# FPGA.net
KiCad netlist of a schematic drawn in Altium Designer
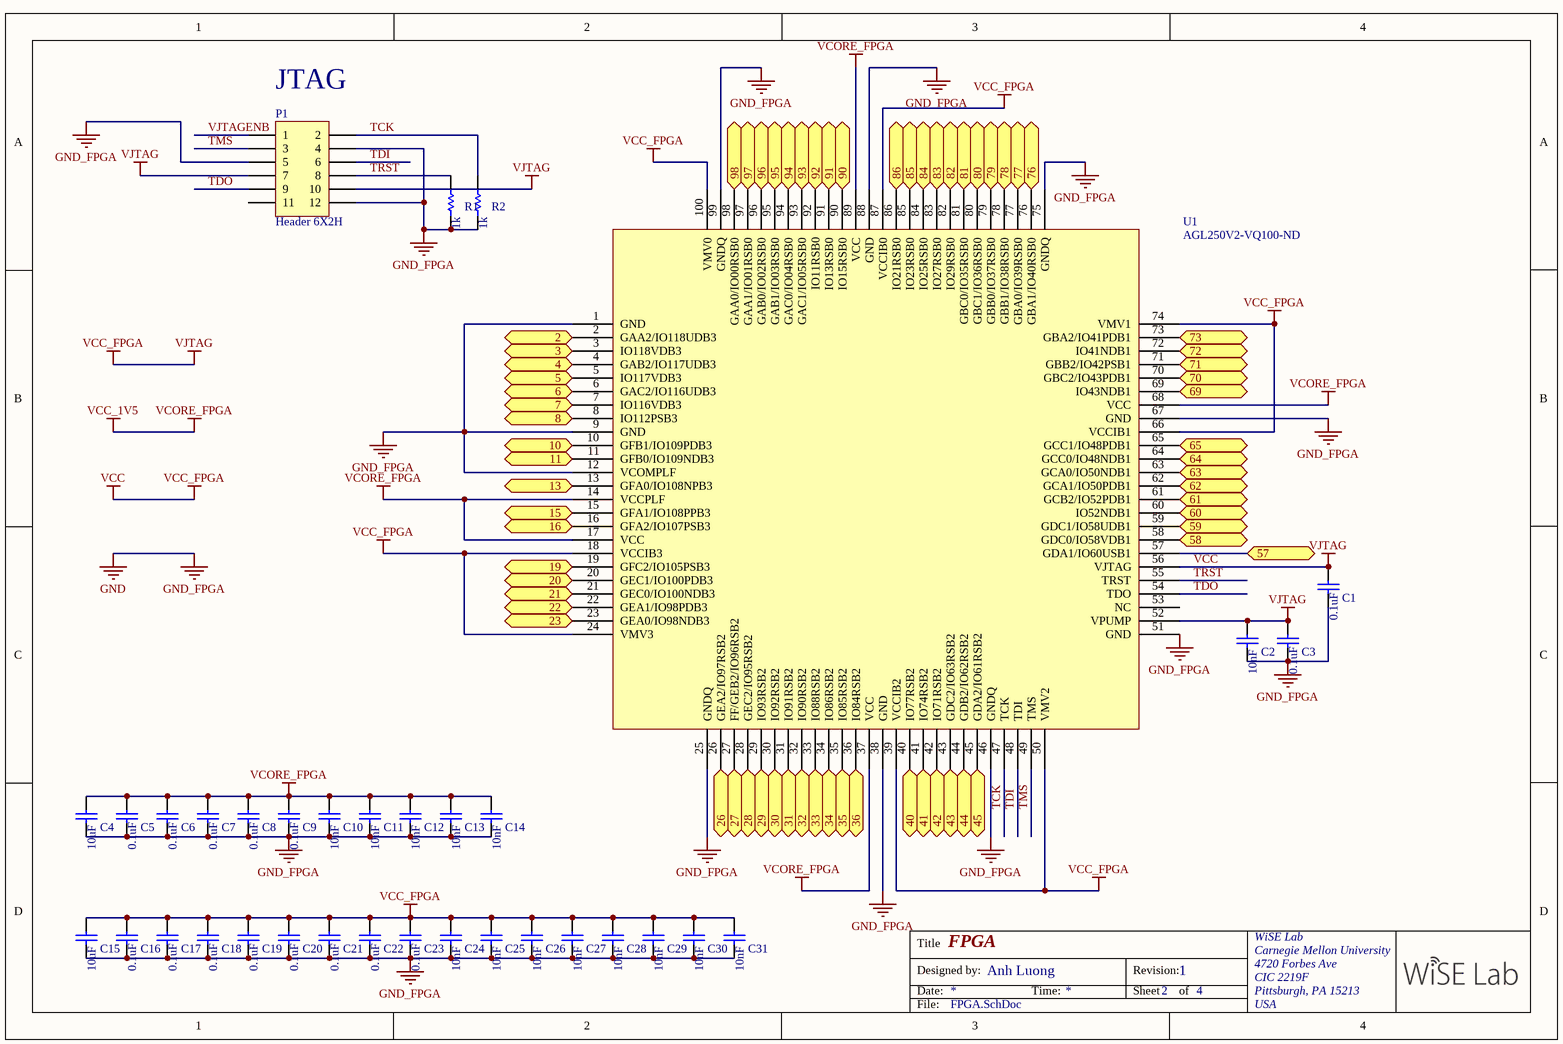
[diagram p0: FPGA.SchDoc]

(export (version "E")
  (design (tool "Eeschema 10.0.6"))
  (components
    (comp (ref "C1")
      (value "GRM155R71C104KA88D")
      (footprint "CAPC1005X04L")
      (description "CAP CER 0.1UF 16V X7R 0402")
      (fields
        (field (name "MANUFACTURER") "Murata Electronics North America")
        (field (name "TOLERANCE") "±10%")
      )
      (libsource (lib "Passives") (part "GRM155R71C104KA88D"))
    )
    (comp (ref "C2")
      (value "GRM155R71E103KA01D")
      (footprint "CAPC1005X04L")
      (description "CAP CER 10000PF 25V X7R 0402")
      (fields
        (field (name "MANUFACTURER") "Murata Electronics North America")
        (field (name "TOLERANCE") "±10%")
      )
      (libsource (lib "Passives") (part "GRM155R71E103KA01D"))
    )
    (comp (ref "C3")
      (value "GRM155R71C104KA88D")
      (footprint "CAPC1005X04L")
      (description "CAP CER 0.1UF 16V X7R 0402")
      (fields
        (field (name "MANUFACTURER") "Murata Electronics North America")
        (field (name "TOLERANCE") "±10%")
      )
      (libsource (lib "Passives") (part "GRM155R71C104KA88D"))
    )
    (comp (ref "C4")
      (value "GRM155R60J106ME15D")
      (footprint "INDC1005X04L")
      (description "CAP CER 10UF 6.3V X5R 0402")
      (fields
        (field (name "MANUFACTURER") "Murata Electronics North America")
        (field (name "TOLERANCE") "±20%")
      )
      (libsource (lib "Passives") (part "GRM155R60J106ME15D"))
    )
    (comp (ref "C5")
      (value "GRM155R71C104KA88D")
      (footprint "CAPC1005X04L")
      (description "CAP CER 0.1UF 16V X7R 0402")
      (fields
        (field (name "MANUFACTURER") "Murata Electronics North America")
        (field (name "TOLERANCE") "±10%")
      )
      (libsource (lib "Passives") (part "GRM155R71C104KA88D"))
    )
    (comp (ref "C6")
      (value "GRM155R71C104KA88D")
      (footprint "CAPC1005X04L")
      (description "CAP CER 0.1UF 16V X7R 0402")
      (fields
        (field (name "MANUFACTURER") "Murata Electronics North America")
        (field (name "TOLERANCE") "±10%")
      )
      (libsource (lib "Passives") (part "GRM155R71C104KA88D"))
    )
    (comp (ref "C7")
      (value "GRM155R71C104KA88D")
      (footprint "CAPC1005X04L")
      (description "CAP CER 0.1UF 16V X7R 0402")
      (fields
        (field (name "MANUFACTURER") "Murata Electronics North America")
        (field (name "TOLERANCE") "±10%")
      )
      (libsource (lib "Passives") (part "GRM155R71C104KA88D"))
    )
    (comp (ref "C8")
      (value "GRM155R71C104KA88D")
      (footprint "CAPC1005X04L")
      (description "CAP CER 0.1UF 16V X7R 0402")
      (fields
        (field (name "MANUFACTURER") "Murata Electronics North America")
        (field (name "TOLERANCE") "±10%")
      )
      (libsource (lib "Passives") (part "GRM155R71C104KA88D"))
    )
    (comp (ref "C9")
      (value "GRM155R71C104KA88D")
      (footprint "CAPC1005X04L")
      (description "CAP CER 0.1UF 16V X7R 0402")
      (fields
        (field (name "MANUFACTURER") "Murata Electronics North America")
        (field (name "TOLERANCE") "±10%")
      )
      (libsource (lib "Passives") (part "GRM155R71C104KA88D"))
    )
    (comp (ref "C10")
      (value "GRM155R71E103KA01D")
      (footprint "CAPC1005X04L")
      (description "CAP CER 10000PF 25V X7R 0402")
      (fields
        (field (name "MANUFACTURER") "Murata Electronics North America")
        (field (name "TOLERANCE") "±10%")
      )
      (libsource (lib "Passives") (part "GRM155R71E103KA01D"))
    )
    (comp (ref "C11")
      (value "GRM155R71E103KA01D")
      (footprint "CAPC1005X04L")
      (description "CAP CER 10000PF 25V X7R 0402")
      (fields
        (field (name "MANUFACTURER") "Murata Electronics North America")
        (field (name "TOLERANCE") "±10%")
      )
      (libsource (lib "Passives") (part "GRM155R71E103KA01D"))
    )
    (comp (ref "C12")
      (value "GRM155R71E103KA01D")
      (footprint "CAPC1005X04L")
      (description "CAP CER 10000PF 25V X7R 0402")
      (fields
        (field (name "MANUFACTURER") "Murata Electronics North America")
        (field (name "TOLERANCE") "±10%")
      )
      (libsource (lib "Passives") (part "GRM155R71E103KA01D"))
    )
    (comp (ref "C13")
      (value "GRM155R71E103KA01D")
      (footprint "CAPC1005X04L")
      (description "CAP CER 10000PF 25V X7R 0402")
      (fields
        (field (name "MANUFACTURER") "Murata Electronics North America")
        (field (name "TOLERANCE") "±10%")
      )
      (libsource (lib "Passives") (part "GRM155R71E103KA01D"))
    )
    (comp (ref "C14")
      (value "GRM155R71E103KA01D")
      (footprint "CAPC1005X04L")
      (description "CAP CER 10000PF 25V X7R 0402")
      (fields
        (field (name "MANUFACTURER") "Murata Electronics North America")
        (field (name "TOLERANCE") "±10%")
      )
      (libsource (lib "Passives") (part "GRM155R71E103KA01D"))
    )
    (comp (ref "C15")
      (value "GRM155R60J106ME15D")
      (footprint "INDC1005X04L")
      (description "CAP CER 10UF 6.3V X5R 0402")
      (fields
        (field (name "MANUFACTURER") "Murata Electronics North America")
        (field (name "TOLERANCE") "±20%")
      )
      (libsource (lib "Passives") (part "GRM155R60J106ME15D"))
    )
    (comp (ref "C16")
      (value "GRM155R71C104KA88D")
      (footprint "CAPC1005X04L")
      (description "CAP CER 0.1UF 16V X7R 0402")
      (fields
        (field (name "MANUFACTURER") "Murata Electronics North America")
        (field (name "TOLERANCE") "±10%")
      )
      (libsource (lib "Passives") (part "GRM155R71C104KA88D"))
    )
    (comp (ref "C17")
      (value "GRM155R71C104KA88D")
      (footprint "CAPC1005X04L")
      (description "CAP CER 0.1UF 16V X7R 0402")
      (fields
        (field (name "MANUFACTURER") "Murata Electronics North America")
        (field (name "TOLERANCE") "±10%")
      )
      (libsource (lib "Passives") (part "GRM155R71C104KA88D"))
    )
    (comp (ref "C18")
      (value "GRM155R71C104KA88D")
      (footprint "CAPC1005X04L")
      (description "CAP CER 0.1UF 16V X7R 0402")
      (fields
        (field (name "MANUFACTURER") "Murata Electronics North America")
        (field (name "TOLERANCE") "±10%")
      )
      (libsource (lib "Passives") (part "GRM155R71C104KA88D"))
    )
    (comp (ref "C19")
      (value "GRM155R71C104KA88D")
      (footprint "CAPC1005X04L")
      (description "CAP CER 0.1UF 16V X7R 0402")
      (fields
        (field (name "MANUFACTURER") "Murata Electronics North America")
        (field (name "TOLERANCE") "±10%")
      )
      (libsource (lib "Passives") (part "GRM155R71C104KA88D"))
    )
    (comp (ref "C20")
      (value "GRM155R71C104KA88D")
      (footprint "CAPC1005X04L")
      (description "CAP CER 0.1UF 16V X7R 0402")
      (fields
        (field (name "MANUFACTURER") "Murata Electronics North America")
        (field (name "TOLERANCE") "±10%")
      )
      (libsource (lib "Passives") (part "GRM155R71C104KA88D"))
    )
    (comp (ref "C21")
      (value "GRM155R71C104KA88D")
      (footprint "CAPC1005X04L")
      (description "CAP CER 0.1UF 16V X7R 0402")
      (fields
        (field (name "MANUFACTURER") "Murata Electronics North America")
        (field (name "TOLERANCE") "±10%")
      )
      (libsource (lib "Passives") (part "GRM155R71C104KA88D"))
    )
    (comp (ref "C22")
      (value "GRM155R71C104KA88D")
      (footprint "CAPC1005X04L")
      (description "CAP CER 0.1UF 16V X7R 0402")
      (fields
        (field (name "MANUFACTURER") "Murata Electronics North America")
        (field (name "TOLERANCE") "±10%")
      )
      (libsource (lib "Passives") (part "GRM155R71C104KA88D"))
    )
    (comp (ref "C23")
      (value "GRM155R71C104KA88D")
      (footprint "CAPC1005X04L")
      (description "CAP CER 0.1UF 16V X7R 0402")
      (fields
        (field (name "MANUFACTURER") "Murata Electronics North America")
        (field (name "TOLERANCE") "±10%")
      )
      (libsource (lib "Passives") (part "GRM155R71C104KA88D"))
    )
    (comp (ref "C24")
      (value "GRM155R71E103KA01D")
      (footprint "CAPC1005X04L")
      (description "CAP CER 10000PF 25V X7R 0402")
      (fields
        (field (name "MANUFACTURER") "Murata Electronics North America")
        (field (name "TOLERANCE") "±10%")
      )
      (libsource (lib "Passives") (part "GRM155R71E103KA01D"))
    )
    (comp (ref "C25")
      (value "GRM155R71E103KA01D")
      (footprint "CAPC1005X04L")
      (description "CAP CER 10000PF 25V X7R 0402")
      (fields
        (field (name "MANUFACTURER") "Murata Electronics North America")
        (field (name "TOLERANCE") "±10%")
      )
      (libsource (lib "Passives") (part "GRM155R71E103KA01D"))
    )
    (comp (ref "C26")
      (value "GRM155R71E103KA01D")
      (footprint "CAPC1005X04L")
      (description "CAP CER 10000PF 25V X7R 0402")
      (fields
        (field (name "MANUFACTURER") "Murata Electronics North America")
        (field (name "TOLERANCE") "±10%")
      )
      (libsource (lib "Passives") (part "GRM155R71E103KA01D"))
    )
    (comp (ref "C27")
      (value "GRM155R71E103KA01D")
      (footprint "CAPC1005X04L")
      (description "CAP CER 10000PF 25V X7R 0402")
      (fields
        (field (name "MANUFACTURER") "Murata Electronics North America")
        (field (name "TOLERANCE") "±10%")
      )
      (libsource (lib "Passives") (part "GRM155R71E103KA01D"))
    )
    (comp (ref "C28")
      (value "GRM155R71E103KA01D")
      (footprint "CAPC1005X04L")
      (description "CAP CER 10000PF 25V X7R 0402")
      (fields
        (field (name "MANUFACTURER") "Murata Electronics North America")
        (field (name "TOLERANCE") "±10%")
      )
      (libsource (lib "Passives") (part "GRM155R71E103KA01D"))
    )
    (comp (ref "C29")
      (value "GRM155R71E103KA01D")
      (footprint "CAPC1005X04L")
      (description "CAP CER 10000PF 25V X7R 0402")
      (fields
        (field (name "MANUFACTURER") "Murata Electronics North America")
        (field (name "TOLERANCE") "±10%")
      )
      (libsource (lib "Passives") (part "GRM155R71E103KA01D"))
    )
    (comp (ref "C30")
      (value "GRM155R71E103KA01D")
      (footprint "CAPC1005X04L")
      (description "CAP CER 10000PF 25V X7R 0402")
      (fields
        (field (name "MANUFACTURER") "Murata Electronics North America")
        (field (name "TOLERANCE") "±10%")
      )
      (libsource (lib "Passives") (part "GRM155R71E103KA01D"))
    )
    (comp (ref "C31")
      (value "GRM155R71E103KA01D")
      (footprint "CAPC1005X04L")
      (description "CAP CER 10000PF 25V X7R 0402")
      (fields
        (field (name "MANUFACTURER") "Murata Electronics North America")
        (field (name "TOLERANCE") "±10%")
      )
      (libsource (lib "Passives") (part "GRM155R71E103KA01D"))
    )
    (comp (ref "P1")
      (value "Header 6X2H")
      (footprint "HDR2X6H")
      (description "Header, 6-Pin, Dual row, Right Angle")
      (fields (field (name "PUBLISHER") "Altium Limited"))
      (libsource (lib "Miscellaneous Connectors") (part "Header 6X2H"))
    )
    (comp (ref "R1")
      (value "MCR01MRTF1001")
      (footprint "RESC1005X04N")
      (description "RES SMD 1K OHM 1% 1/16W 0402")
      (fields (field (name "MANUFACTURER") "Rohm Semiconductor") (field (name "TOLERANCE") "±1%"))
      (libsource (lib "Passives") (part "MCR01MRTF1001"))
    )
    (comp (ref "R2")
      (value "MCR01MRTF1001")
      (footprint "RESC1005X04N")
      (description "RES SMD 1K OHM 1% 1/16W 0402")
      (fields (field (name "MANUFACTURER") "Rohm Semiconductor") (field (name "TOLERANCE") "±1%"))
      (libsource (lib "Passives") (part "MCR01MRTF1001"))
    )
    (comp (ref "U1")
      (value "AGL250V2-VQ100")
      (footprint "TSQFP50P1600X1600X120-100N")
      (description "IC FPGA 68 I/O 100VQFP")
      (fields
        (field (name "MANUFACTURER") "Microsemi SoC")
        (field (name "SUPPLIER PART NUMBER 1") "AGL250V2-VQ100-ND")
      )
      (libsource (lib "Chronos") (part "AGL250V2-VQ100"))
    )
  )
  (nets
    (net (code "1") (name "/2") (class "Default")
      (node (ref "U1") (pin "2") (pinfunction "GAA2/IO118UDB3_2") (pintype "passive"))
    )
    (net (code "2") (name "/3") (class "Default")
      (node (ref "U1") (pin "3") (pinfunction "IO118VDB3_3") (pintype "passive"))
    )
    (net (code "3") (name "/4") (class "Default")
      (node (ref "U1") (pin "4") (pinfunction "GAB2/IO117UDB3_4") (pintype "passive"))
    )
    (net (code "4") (name "/5") (class "Default")
      (node (ref "U1") (pin "5") (pinfunction "IO117VDB3_5") (pintype "passive"))
    )
    (net (code "5") (name "/6") (class "Default")
      (node (ref "U1") (pin "6") (pinfunction "GAC2/IO116UDB3_6") (pintype "passive"))
    )
    (net (code "6") (name "/7") (class "Default")
      (node (ref "U1") (pin "7") (pinfunction "IO116VDB3_7") (pintype "passive"))
    )
    (net (code "7") (name "/8") (class "Default")
      (node (ref "U1") (pin "8") (pinfunction "IO112PSB3_8") (pintype "passive"))
    )
    (net (code "8") (name "/10") (class "Default")
      (node (ref "U1") (pin "10") (pinfunction "GFB1/IO109PDB3_10") (pintype "passive"))
    )
    (net (code "9") (name "/11") (class "Default")
      (node (ref "U1") (pin "11") (pinfunction "GFB0/IO109NDB3_11") (pintype "passive"))
    )
    (net (code "10") (name "/13") (class "Default")
      (node (ref "U1") (pin "13") (pinfunction "GFA0/IO108NPB3_13") (pintype "passive"))
    )
    (net (code "11") (name "/15") (class "Default")
      (node (ref "U1") (pin "15") (pinfunction "GFA1/IO108PPB3_15") (pintype "passive"))
    )
    (net (code "12") (name "/16") (class "Default")
      (node (ref "U1") (pin "16") (pinfunction "GFA2/IO107PSB3_16") (pintype "passive"))
    )
    (net (code "13") (name "/19") (class "Default")
      (node (ref "U1") (pin "19") (pinfunction "GFC2/IO105PSB3_19") (pintype "passive"))
    )
    (net (code "14") (name "/20") (class "Default")
      (node (ref "U1") (pin "20") (pinfunction "GEC1/IO100PDB3_20") (pintype "passive"))
    )
    (net (code "15") (name "/21") (class "Default")
      (node (ref "U1") (pin "21") (pinfunction "GEC0/IO100NDB3_21") (pintype "passive"))
    )
    (net (code "16") (name "/22") (class "Default")
      (node (ref "U1") (pin "22") (pinfunction "GEA1/IO98PDB3_22") (pintype "passive"))
    )
    (net (code "17") (name "/23") (class "Default")
      (node (ref "U1") (pin "23") (pinfunction "GEA0/IO98NDB3_23") (pintype "passive"))
    )
    (net (code "18") (name "/26") (class "Default")
      (node (ref "U1") (pin "26") (pinfunction "GEA2/IO97RSB2_26") (pintype "passive"))
    )
    (net (code "19") (name "/27") (class "Default")
      (node (ref "U1") (pin "27") (pinfunction "FF/GEB2/IO96RSB2_27") (pintype "passive"))
    )
    (net (code "20") (name "/28") (class "Default")
      (node (ref "U1") (pin "28") (pinfunction "GEC2/IO95RSB2_28") (pintype "passive"))
    )
    (net (code "21") (name "/29") (class "Default")
      (node (ref "U1") (pin "29") (pinfunction "IO93RSB2_29") (pintype "passive"))
    )
    (net (code "22") (name "/30") (class "Default")
      (node (ref "U1") (pin "30") (pinfunction "IO92RSB2_30") (pintype "passive"))
    )
    (net (code "23") (name "/31") (class "Default")
      (node (ref "U1") (pin "31") (pinfunction "IO91RSB2_31") (pintype "passive"))
    )
    (net (code "24") (name "/32") (class "Default")
      (node (ref "U1") (pin "32") (pinfunction "IO90RSB2_32") (pintype "passive"))
    )
    (net (code "25") (name "/33") (class "Default")
      (node (ref "U1") (pin "33") (pinfunction "IO88RSB2_33") (pintype "passive"))
    )
    (net (code "26") (name "/34") (class "Default")
      (node (ref "U1") (pin "34") (pinfunction "IO86RSB2_34") (pintype "passive"))
    )
    (net (code "27") (name "/35") (class "Default")
      (node (ref "U1") (pin "35") (pinfunction "IO85RSB2_35") (pintype "passive"))
    )
    (net (code "28") (name "/36") (class "Default")
      (node (ref "U1") (pin "36") (pinfunction "IO84RSB2_36") (pintype "passive"))
    )
    (net (code "29") (name "/40") (class "Default")
      (node (ref "U1") (pin "40") (pinfunction "IO77RSB2_40") (pintype "passive"))
    )
    (net (code "30") (name "/41") (class "Default")
      (node (ref "U1") (pin "41") (pinfunction "IO74RSB2_41") (pintype "passive"))
    )
    (net (code "31") (name "/42") (class "Default")
      (node (ref "U1") (pin "42") (pinfunction "IO71RSB2_42") (pintype "passive"))
    )
    (net (code "32") (name "/43") (class "Default")
      (node (ref "U1") (pin "43") (pinfunction "GDC2/IO63RSB2_43") (pintype "passive"))
    )
    (net (code "33") (name "/44") (class "Default")
      (node (ref "U1") (pin "44") (pinfunction "GDB2/IO62RSB2_44") (pintype "passive"))
    )
    (net (code "34") (name "/45") (class "Default")
      (node (ref "U1") (pin "45") (pinfunction "GDA2/IO61RSB2_45") (pintype "passive"))
    )
    (net (code "35") (name "/57") (class "Default")
      (node (ref "U1") (pin "57") (pinfunction "GDA1/IO60USB1_57") (pintype "passive"))
    )
    (net (code "36") (name "/58") (class "Default")
      (node (ref "U1") (pin "58") (pinfunction "GDC0/IO58VDB1_58") (pintype "passive"))
    )
    (net (code "37") (name "/59") (class "Default")
      (node (ref "U1") (pin "59") (pinfunction "GDC1/IO58UDB1_59") (pintype "passive"))
    )
    (net (code "38") (name "/60") (class "Default")
      (node (ref "U1") (pin "60") (pinfunction "IO52NDB1_60") (pintype "passive"))
    )
    (net (code "39") (name "/61") (class "Default")
      (node (ref "U1") (pin "61") (pinfunction "GCB2/IO52PDB1_61") (pintype "passive"))
    )
    (net (code "40") (name "/62") (class "Default")
      (node (ref "U1") (pin "62") (pinfunction "GCA1/IO50PDB1_62") (pintype "passive"))
    )
    (net (code "41") (name "/63") (class "Default")
      (node (ref "U1") (pin "63") (pinfunction "GCA0/IO50NDB1_63") (pintype "passive"))
    )
    (net (code "42") (name "/64") (class "Default")
      (node (ref "U1") (pin "64") (pinfunction "GCC0/IO48NDB1_64") (pintype "passive"))
    )
    (net (code "43") (name "/65") (class "Default")
      (node (ref "U1") (pin "65") (pinfunction "GCC1/IO48PDB1_65") (pintype "passive"))
    )
    (net (code "44") (name "/69") (class "Default")
      (node (ref "U1") (pin "69") (pinfunction "IO43NDB1_69") (pintype "passive"))
    )
    (net (code "45") (name "/70") (class "Default")
      (node (ref "U1") (pin "70") (pinfunction "GBC2/IO43PDB1_70") (pintype "passive"))
    )
    (net (code "46") (name "/71") (class "Default")
      (node (ref "U1") (pin "71") (pinfunction "GBB2/IO42PSB1_71") (pintype "passive"))
    )
    (net (code "47") (name "/72") (class "Default")
      (node (ref "U1") (pin "72") (pinfunction "IO41NDB1_72") (pintype "passive"))
    )
    (net (code "48") (name "/73") (class "Default")
      (node (ref "U1") (pin "73") (pinfunction "GBA2/IO41PDB1_73") (pintype "passive"))
    )
    (net (code "49") (name "/76") (class "Default")
      (node (ref "U1") (pin "76") (pinfunction "GBA1/IO40RSB0_76") (pintype "passive"))
    )
    (net (code "50") (name "/77") (class "Default")
      (node (ref "U1") (pin "77") (pinfunction "GBA0/IO39RSB0_77") (pintype "passive"))
    )
    (net (code "51") (name "/78") (class "Default")
      (node (ref "U1") (pin "78") (pinfunction "GBB1/IO38RSB0_78") (pintype "passive"))
    )
    (net (code "52") (name "/79") (class "Default")
      (node (ref "U1") (pin "79") (pinfunction "GBB0/IO37RSB0_79") (pintype "passive"))
    )
    (net (code "53") (name "/80") (class "Default")
      (node (ref "U1") (pin "80") (pinfunction "GBC1/IO36RSB0_80") (pintype "passive"))
    )
    (net (code "54") (name "/81") (class "Default")
      (node (ref "U1") (pin "81") (pinfunction "GBC0/IO35RSB0_81") (pintype "passive"))
    )
    (net (code "55") (name "/82") (class "Default")
      (node (ref "U1") (pin "82") (pinfunction "IO29RSB0_82") (pintype "passive"))
    )
    (net (code "56") (name "/83") (class "Default")
      (node (ref "U1") (pin "83") (pinfunction "IO27RSB0_83") (pintype "passive"))
    )
    (net (code "57") (name "/84") (class "Default")
      (node (ref "U1") (pin "84") (pinfunction "IO25RSB0_84") (pintype "passive"))
    )
    (net (code "58") (name "/85") (class "Default")
      (node (ref "U1") (pin "85") (pinfunction "IO23RSB0_85") (pintype "passive"))
    )
    (net (code "59") (name "/86") (class "Default")
      (node (ref "U1") (pin "86") (pinfunction "IO21RSB0_86") (pintype "passive"))
    )
    (net (code "60") (name "/90") (class "Default")
      (node (ref "U1") (pin "90") (pinfunction "IO15RSB0_90") (pintype "passive"))
    )
    (net (code "61") (name "/91") (class "Default")
      (node (ref "U1") (pin "91") (pinfunction "IO13RSB0_91") (pintype "passive"))
    )
    (net (code "62") (name "/92") (class "Default")
      (node (ref "U1") (pin "92") (pinfunction "IO11RSB0_92") (pintype "passive"))
    )
    (net (code "63") (name "/93") (class "Default")
      (node (ref "U1") (pin "93") (pinfunction "GAC1/IO05RSB0_93") (pintype "passive"))
    )
    (net (code "64") (name "/94") (class "Default")
      (node (ref "U1") (pin "94") (pinfunction "GAC0/IO04RSB0_94") (pintype "passive"))
    )
    (net (code "65") (name "/95") (class "Default")
      (node (ref "U1") (pin "95") (pinfunction "GAB1/IO03RSB0_95") (pintype "passive"))
    )
    (net (code "66") (name "/96") (class "Default")
      (node (ref "U1") (pin "96") (pinfunction "GAB0/IO02RSB0_96") (pintype "passive"))
    )
    (net (code "67") (name "/97") (class "Default")
      (node (ref "U1") (pin "97") (pinfunction "GAA1/IO01RSB0_97") (pintype "passive"))
    )
    (net (code "68") (name "/98") (class "Default")
      (node (ref "U1") (pin "98") (pinfunction "GAA0/IO00RSB0_98") (pintype "passive"))
    )
    (net (code "69") (name "/TCK") (class "Default")
      (node (ref "P1") (pin "2") (pinfunction "2_2") (pintype "passive"))
      (node (ref "R2") (pin "2") (pinfunction "2_2") (pintype "passive"))
      (node (ref "U1") (pin "47") (pinfunction "TCK_47") (pintype "passive"))
    )
    (net (code "70") (name "/TDI") (class "Default")
      (node (ref "P1") (pin "6") (pinfunction "6_6") (pintype "passive"))
      (node (ref "U1") (pin "48") (pinfunction "TDI_48") (pintype "passive"))
    )
    (net (code "71") (name "/TDO") (class "Default")
      (node (ref "P1") (pin "9") (pinfunction "9_9") (pintype "passive"))
      (node (ref "U1") (pin "54") (pinfunction "TDO_54") (pintype "passive"))
    )
    (net (code "72") (name "/TMS") (class "Default")
      (node (ref "P1") (pin "3") (pinfunction "3_3") (pintype "passive"))
      (node (ref "U1") (pin "49") (pinfunction "TMS_49") (pintype "passive"))
    )
    (net (code "73") (name "/TRST") (class "Default")
      (node (ref "P1") (pin "8") (pinfunction "8_8") (pintype "passive"))
      (node (ref "R1") (pin "2") (pinfunction "2_2") (pintype "passive"))
      (node (ref "U1") (pin "55") (pinfunction "TRST_55") (pintype "passive"))
    )
    (net (code "74") (name "/VJTAGENB") (class "Default")
      (node (ref "P1") (pin "1") (pinfunction "1_1") (pintype "passive"))
    )
    (net (code "75") (name "GND") (class "Default")
      (node (ref "C1") (pin "1") (pinfunction "1_1") (pintype "passive"))
      (node (ref "C10") (pin "1") (pinfunction "1_1") (pintype "passive"))
      (node (ref "C11") (pin "1") (pinfunction "1_1") (pintype "passive"))
      (node (ref "C12") (pin "1") (pinfunction "1_1") (pintype "passive"))
      (node (ref "C13") (pin "1") (pinfunction "1_1") (pintype "passive"))
      (node (ref "C14") (pin "1") (pinfunction "1_1") (pintype "passive"))
      (node (ref "C15") (pin "1") (pinfunction "1_1") (pintype "passive"))
      (node (ref "C16") (pin "1") (pinfunction "1_1") (pintype "passive"))
      (node (ref "C17") (pin "1") (pinfunction "1_1") (pintype "passive"))
      (node (ref "C18") (pin "1") (pinfunction "1_1") (pintype "passive"))
      (node (ref "C19") (pin "1") (pinfunction "1_1") (pintype "passive"))
      (node (ref "C2") (pin "1") (pinfunction "1_1") (pintype "passive"))
      (node (ref "C20") (pin "1") (pinfunction "1_1") (pintype "passive"))
      (node (ref "C21") (pin "1") (pinfunction "1_1") (pintype "passive"))
      (node (ref "C22") (pin "1") (pinfunction "1_1") (pintype "passive"))
      (node (ref "C23") (pin "1") (pinfunction "1_1") (pintype "passive"))
      (node (ref "C24") (pin "1") (pinfunction "1_1") (pintype "passive"))
      (node (ref "C25") (pin "1") (pinfunction "1_1") (pintype "passive"))
      (node (ref "C26") (pin "1") (pinfunction "1_1") (pintype "passive"))
      (node (ref "C27") (pin "1") (pinfunction "1_1") (pintype "passive"))
      (node (ref "C28") (pin "1") (pinfunction "1_1") (pintype "passive"))
      (node (ref "C29") (pin "1") (pinfunction "1_1") (pintype "passive"))
      (node (ref "C3") (pin "1") (pinfunction "1_1") (pintype "passive"))
      (node (ref "C30") (pin "1") (pinfunction "1_1") (pintype "passive"))
      (node (ref "C31") (pin "1") (pinfunction "1_1") (pintype "passive"))
      (node (ref "C4") (pin "1") (pinfunction "1_1") (pintype "passive"))
      (node (ref "C5") (pin "1") (pinfunction "1_1") (pintype "passive"))
      (node (ref "C6") (pin "1") (pinfunction "1_1") (pintype "passive"))
      (node (ref "C7") (pin "1") (pinfunction "1_1") (pintype "passive"))
      (node (ref "C8") (pin "1") (pinfunction "1_1") (pintype "passive"))
      (node (ref "C9") (pin "1") (pinfunction "1_1") (pintype "passive"))
      (node (ref "P1") (pin "12") (pinfunction "12_12") (pintype "passive"))
      (node (ref "P1") (pin "4") (pinfunction "4_4") (pintype "passive"))
      (node (ref "P1") (pin "5") (pinfunction "5_5") (pintype "passive"))
      (node (ref "R1") (pin "1") (pinfunction "1_1") (pintype "passive"))
      (node (ref "R2") (pin "1") (pinfunction "1_1") (pintype "passive"))
      (node (ref "U1") (pin "1") (pinfunction "GND_1") (pintype "passive"))
      (node (ref "U1") (pin "12") (pinfunction "VCOMPLF_12") (pintype "passive"))
      (node (ref "U1") (pin "25") (pinfunction "GNDQ_25") (pintype "passive"))
      (node (ref "U1") (pin "38") (pinfunction "GND_38") (pintype "passive"))
      (node (ref "U1") (pin "46") (pinfunction "GNDQ_46") (pintype "passive"))
      (node (ref "U1") (pin "51") (pinfunction "GND_51") (pintype "passive"))
      (node (ref "U1") (pin "67") (pinfunction "GND_67") (pintype "passive"))
      (node (ref "U1") (pin "75") (pinfunction "GNDQ_75") (pintype "passive"))
      (node (ref "U1") (pin "88") (pinfunction "GND_88") (pintype "passive"))
      (node (ref "U1") (pin "9") (pinfunction "GND_9") (pintype "passive"))
      (node (ref "U1") (pin "99") (pinfunction "GNDQ_99") (pintype "passive"))
    )
    (net (code "76") (name "VCC") (class "Default")
      (node (ref "C1") (pin "2") (pinfunction "2_2") (pintype "passive"))
      (node (ref "C15") (pin "2") (pinfunction "2_2") (pintype "passive"))
      (node (ref "C16") (pin "2") (pinfunction "2_2") (pintype "passive"))
      (node (ref "C17") (pin "2") (pinfunction "2_2") (pintype "passive"))
      (node (ref "C18") (pin "2") (pinfunction "2_2") (pintype "passive"))
      (node (ref "C19") (pin "2") (pinfunction "2_2") (pintype "passive"))
      (node (ref "C2") (pin "2") (pinfunction "2_2") (pintype "passive"))
      (node (ref "C20") (pin "2") (pinfunction "2_2") (pintype "passive"))
      (node (ref "C21") (pin "2") (pinfunction "2_2") (pintype "passive"))
      (node (ref "C22") (pin "2") (pinfunction "2_2") (pintype "passive"))
      (node (ref "C23") (pin "2") (pinfunction "2_2") (pintype "passive"))
      (node (ref "C24") (pin "2") (pinfunction "2_2") (pintype "passive"))
      (node (ref "C25") (pin "2") (pinfunction "2_2") (pintype "passive"))
      (node (ref "C26") (pin "2") (pinfunction "2_2") (pintype "passive"))
      (node (ref "C27") (pin "2") (pinfunction "2_2") (pintype "passive"))
      (node (ref "C28") (pin "2") (pinfunction "2_2") (pintype "passive"))
      (node (ref "C29") (pin "2") (pinfunction "2_2") (pintype "passive"))
      (node (ref "C3") (pin "2") (pinfunction "2_2") (pintype "passive"))
      (node (ref "C30") (pin "2") (pinfunction "2_2") (pintype "passive"))
      (node (ref "C31") (pin "2") (pinfunction "2_2") (pintype "passive"))
      (node (ref "P1") (pin "10") (pinfunction "10_10") (pintype "passive"))
      (node (ref "P1") (pin "7") (pinfunction "7_7") (pintype "passive"))
      (node (ref "U1") (pin "100") (pinfunction "VMV0_100") (pintype "passive"))
      (node (ref "U1") (pin "18") (pinfunction "VCCIB3_18") (pintype "passive"))
      (node (ref "U1") (pin "24") (pinfunction "VMV3_24") (pintype "passive"))
      (node (ref "U1") (pin "39") (pinfunction "VCCIB2_39") (pintype "passive"))
      (node (ref "U1") (pin "50") (pinfunction "VMV2_50") (pintype "passive"))
      (node (ref "U1") (pin "52") (pinfunction "VPUMP_52") (pintype "passive"))
      (node (ref "U1") (pin "56") (pinfunction "VJTAG_56") (pintype "passive"))
      (node (ref "U1") (pin "66") (pinfunction "VCCIB1_66") (pintype "passive"))
      (node (ref "U1") (pin "74") (pinfunction "VMV1_74") (pintype "passive"))
      (node (ref "U1") (pin "87") (pinfunction "VCCIB0_87") (pintype "passive"))
    )
    (net (code "77") (name "VCC_1V5") (class "Default")
      (node (ref "C10") (pin "2") (pinfunction "2_2") (pintype "passive"))
      (node (ref "C11") (pin "2") (pinfunction "2_2") (pintype "passive"))
      (node (ref "C12") (pin "2") (pinfunction "2_2") (pintype "passive"))
      (node (ref "C13") (pin "2") (pinfunction "2_2") (pintype "passive"))
      (node (ref "C14") (pin "2") (pinfunction "2_2") (pintype "passive"))
      (node (ref "C4") (pin "2") (pinfunction "2_2") (pintype "passive"))
      (node (ref "C5") (pin "2") (pinfunction "2_2") (pintype "passive"))
      (node (ref "C6") (pin "2") (pinfunction "2_2") (pintype "passive"))
      (node (ref "C7") (pin "2") (pinfunction "2_2") (pintype "passive"))
      (node (ref "C8") (pin "2") (pinfunction "2_2") (pintype "passive"))
      (node (ref "C9") (pin "2") (pinfunction "2_2") (pintype "passive"))
      (node (ref "U1") (pin "14") (pinfunction "VCCPLF_14") (pintype "passive"))
      (node (ref "U1") (pin "17") (pinfunction "VCC_17") (pintype "passive"))
      (node (ref "U1") (pin "37") (pinfunction "VCC_37") (pintype "passive"))
      (node (ref "U1") (pin "68") (pinfunction "VCC_68") (pintype "passive"))
      (node (ref "U1") (pin "89") (pinfunction "VCC_89") (pintype "passive"))
    )
    (net (code "78") (name "unconnected-(P1-Pad11)") (class "Default")
      (node (ref "P1") (pin "11") (pinfunction "11_11") (pintype "passive"))
    )
    (net (code "79") (name "unconnected-(U1-NC-Pad53)") (class "Default")
      (node (ref "U1") (pin "53") (pinfunction "NC_53") (pintype "passive"))
    )
  )
)
